# Processor.net
KiCad netlist of a schematic drawn in Altium Designer
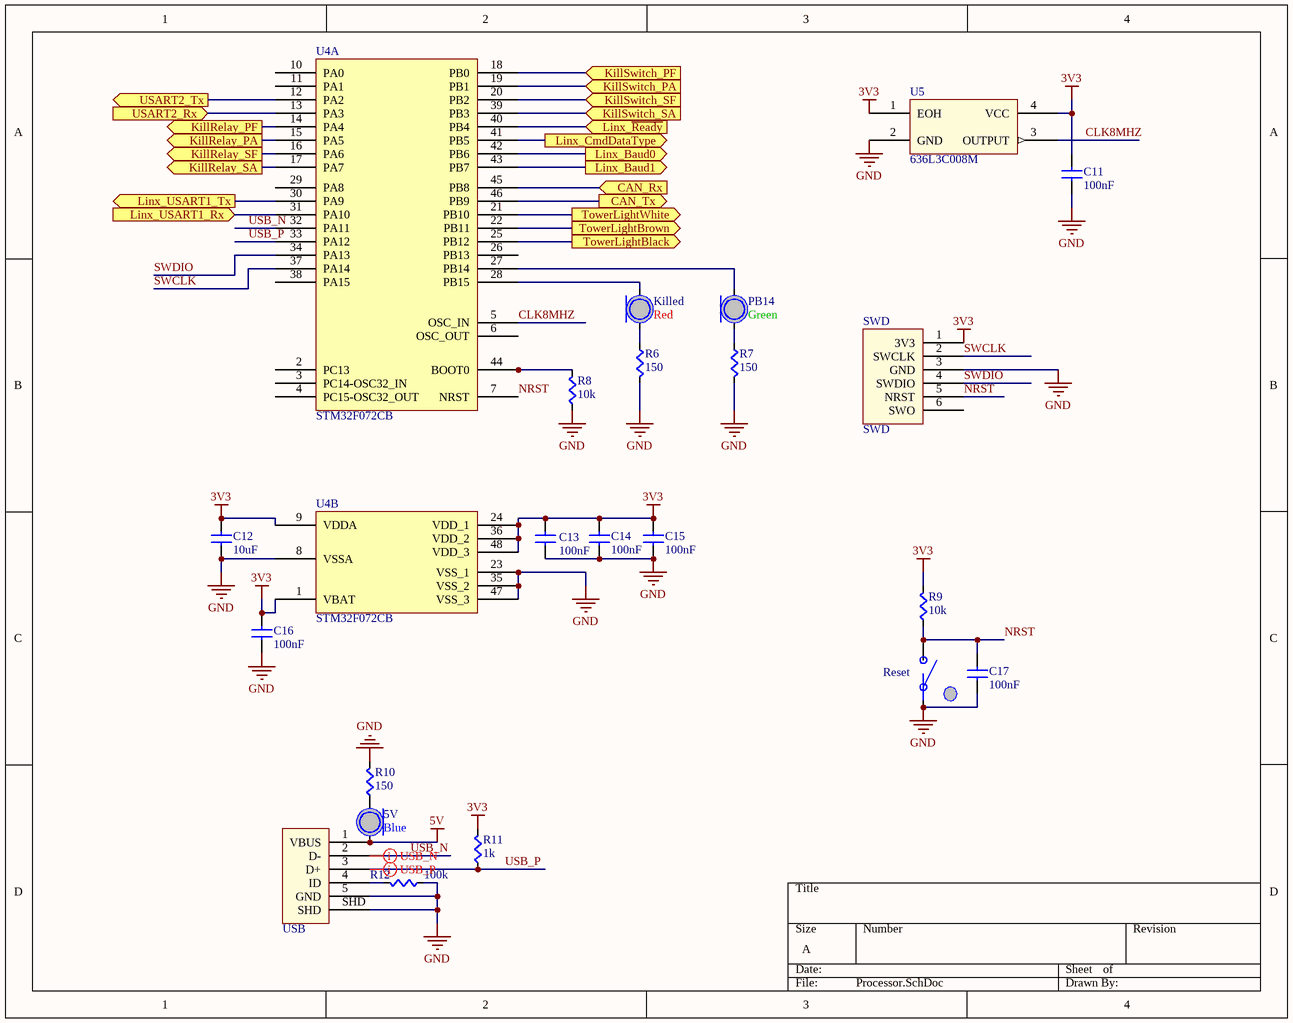
[diagram p0: Processor.SchDoc]

(export (version "E")
  (design (tool "Eeschema 10.0.6"))
  (components
    (comp (ref "5V")
      (value "LED")
      (footprint "LED0603")
      (fields (field (name "COLOR") "Blue"))
      (libsource (lib "") (part "LED_1"))
    )
    (comp (ref "C11")
      (value "100nF")
      (footprint "CAPC0603")
      (fields (field (name "Comment") "Cap"))
      (libsource (lib "SubjuGator8") (part "Cap"))
    )
    (comp (ref "C12")
      (value "10uF")
      (footprint "CAPC0603")
      (fields (field (name "Comment") "Cap"))
      (libsource (lib "SubjuGator8") (part "Cap"))
    )
    (comp (ref "C13")
      (value "100nF")
      (footprint "CAPC0603")
      (fields (field (name "Comment") "Cap"))
      (libsource (lib "SubjuGator8") (part "Cap"))
    )
    (comp (ref "C14")
      (value "100nF")
      (footprint "CAPC0603")
      (fields (field (name "Comment") "Cap"))
      (libsource (lib "SubjuGator8") (part "Cap"))
    )
    (comp (ref "C15")
      (value "100nF")
      (footprint "CAPC0603")
      (fields (field (name "Comment") "Cap"))
      (libsource (lib "SubjuGator8") (part "Cap"))
    )
    (comp (ref "C16")
      (value "100nF")
      (footprint "CAPC0603")
      (fields (field (name "Comment") "Cap"))
      (libsource (lib "SubjuGator8") (part "Cap"))
    )
    (comp (ref "C17")
      (value "100nF")
      (footprint "CAPC0603")
      (fields (field (name "Comment") "Cap"))
      (libsource (lib "SubjuGator8") (part "Cap"))
    )
    (comp (ref "Killed")
      (value "LED")
      (footprint "LED0603")
      (fields (field (name "COLOR") "Red"))
      (libsource (lib "SubjuGator8") (part "LED"))
    )
    (comp (ref "PB14")
      (value "LED")
      (footprint "LED0603")
      (fields (field (name "COLOR") "Green"))
      (libsource (lib "SubjuGator8") (part "LED"))
    )
    (comp (ref "R6")
      (value "150")
      (footprint "RES0603")
      (fields (field (name "Comment") "Res"))
      (libsource (lib "SubjuGator8") (part "Res"))
    )
    (comp (ref "R7")
      (value "150")
      (footprint "RES0603")
      (fields (field (name "Comment") "Res"))
      (libsource (lib "SubjuGator8") (part "Res"))
    )
    (comp (ref "R8")
      (value "10k")
      (footprint "RES0603")
      (fields (field (name "Comment") "Res"))
      (libsource (lib "SubjuGator8") (part "Res"))
    )
    (comp (ref "R9")
      (value "10k")
      (footprint "RES0603")
      (fields (field (name "Comment") "Res"))
      (libsource (lib "SubjuGator8") (part "Res"))
    )
    (comp (ref "R10")
      (value "150")
      (footprint "RES0603")
      (fields (field (name "Comment") "Res"))
      (libsource (lib "SubjuGator8") (part "Res"))
    )
    (comp (ref "R11")
      (value "1k")
      (footprint "RES0603")
      (fields (field (name "Comment") "Res"))
      (libsource (lib "SubjuGator8") (part "Res"))
    )
    (comp (ref "R12")
      (value "100k")
      (footprint "RES0603")
      (fields (field (name "Comment") "Res"))
      (libsource (lib "SubjuGator8") (part "Res"))
    )
    (comp (ref "Reset")
      (value "Button")
      (footprint "PTS645xxxxSMTR92")
      (description "SPST Button")
      (libsource (lib "SubjuGator8") (part "Button"))
    )
    (comp (ref "SWD")
      (value "SWD")
      (footprint "SWD_STM32")
      (description "SWD connector matching the pinout on STM Discovery Boards")
      (libsource (lib "SubjuGator8") (part "SWD_STM32"))
    )
    (comp (ref "U4")
      (value "STM32F072CB")
      (footprint "STM32F072CB")
      (description "MCU 32BIT 128KB FLASH 48LQFP")
      (libsource (lib "ICs") (part "STM32F072CB"))
    )
    (comp (ref "U5")
      (value "636L3C008M")
      (footprint "636L3C")
      (description "HCMOS/TTL Clock Oscillator")
      (libsource (lib "SubjuGator8") (part "636L3C"))
    )
    (comp (ref "USB")
      (value "USB Micro")
      (footprint "10118192-0001LF")
      (description "USB Mini B Metal Shield SMT")
      (libsource (lib "SubjuGator8") (part "USB Micro"))
    )
  )
  (nets
    (net (code "1") (name "/CAN_Rx") (class "Default")
      (node (ref "U4") (pin "45") (pinfunction "PB8_45") (pintype "passive"))
    )
    (net (code "2") (name "/CAN_Tx") (class "Default")
      (node (ref "U4") (pin "46") (pinfunction "PB9_46") (pintype "passive"))
    )
    (net (code "3") (name "/CLK8MHZ") (class "Default")
      (node (ref "U4") (pin "5") (pinfunction "OSC_IN_5") (pintype "passive"))
      (node (ref "U5") (pin "3") (pinfunction "OUTPUT_3") (pintype "output"))
    )
    (net (code "4") (name "/KillRelay_PA") (class "Default")
      (node (ref "U4") (pin "15") (pinfunction "PA5_15") (pintype "passive"))
    )
    (net (code "5") (name "/KillRelay_PF") (class "Default")
      (node (ref "U4") (pin "14") (pinfunction "PA4_14") (pintype "passive"))
    )
    (net (code "6") (name "/KillRelay_SA") (class "Default")
      (node (ref "U4") (pin "17") (pinfunction "PA7_17") (pintype "passive"))
    )
    (net (code "7") (name "/KillRelay_SF") (class "Default")
      (node (ref "U4") (pin "16") (pinfunction "PA6_16") (pintype "passive"))
    )
    (net (code "8") (name "/KillSwitch_PA") (class "Default")
      (node (ref "U4") (pin "19") (pinfunction "PB1_19") (pintype "passive"))
    )
    (net (code "9") (name "/KillSwitch_PF") (class "Default")
      (node (ref "U4") (pin "18") (pinfunction "PB0_18") (pintype "passive"))
    )
    (net (code "10") (name "/KillSwitch_SA") (class "Default")
      (node (ref "U4") (pin "39") (pinfunction "PB3_39") (pintype "passive"))
    )
    (net (code "11") (name "/KillSwitch_SF") (class "Default")
      (node (ref "U4") (pin "20") (pinfunction "PB2_20") (pintype "passive"))
    )
    (net (code "12") (name "/Linx_Baud0") (class "Default")
      (node (ref "U4") (pin "42") (pinfunction "PB6_42") (pintype "passive"))
    )
    (net (code "13") (name "/Linx_Baud1") (class "Default")
      (node (ref "U4") (pin "43") (pinfunction "PB7_43") (pintype "passive"))
    )
    (net (code "14") (name "/Linx_CmdDataType") (class "Default")
      (node (ref "U4") (pin "41") (pinfunction "PB5_41") (pintype "passive"))
    )
    (net (code "15") (name "/Linx_USART1_Rx") (class "Default")
      (node (ref "U4") (pin "31") (pinfunction "PA10_31") (pintype "passive"))
    )
    (net (code "16") (name "/Linx_USART1_Tx") (class "Default")
      (node (ref "U4") (pin "30") (pinfunction "PA9_30") (pintype "passive"))
    )
    (net (code "17") (name "/Linx_~{Ready}") (class "Default")
      (node (ref "U4") (pin "40") (pinfunction "PB4_40") (pintype "passive"))
    )
    (net (code "18") (name "/NRST") (class "Default")
      (node (ref "C17") (pin "1") (pinfunction "A_1") (pintype "passive"))
      (node (ref "R9") (pin "2") (pinfunction "B_2") (pintype "passive"))
      (node (ref "Reset") (pin "B") (pinfunction "B_B") (pintype "passive"))
      (node (ref "SWD") (pin "5") (pinfunction "NRST_5") (pintype "passive"))
      (node (ref "U4") (pin "7") (pinfunction "NRST_7") (pintype "passive"))
    )
    (net (code "19") (name "/SWCLK") (class "Default")
      (node (ref "SWD") (pin "2") (pinfunction "SWCLK_2") (pintype "passive"))
      (node (ref "U4") (pin "37") (pinfunction "PA14_37") (pintype "passive"))
    )
    (net (code "20") (name "/SWDIO") (class "Default")
      (node (ref "SWD") (pin "4") (pinfunction "SWDIO_4") (pintype "passive"))
      (node (ref "U4") (pin "34") (pinfunction "PA13_34") (pintype "passive"))
    )
    (net (code "21") (name "/TowerLightBlack") (class "Default")
      (node (ref "U4") (pin "25") (pinfunction "PB12_25") (pintype "passive"))
    )
    (net (code "22") (name "/TowerLightBrown") (class "Default")
      (node (ref "U4") (pin "22") (pinfunction "PB11_22") (pintype "passive"))
    )
    (net (code "23") (name "/TowerLightWhite") (class "Default")
      (node (ref "U4") (pin "21") (pinfunction "PB10_21") (pintype "passive"))
    )
    (net (code "24") (name "/USART2_Rx") (class "Default")
      (node (ref "U4") (pin "13") (pinfunction "PA3_13") (pintype "passive"))
    )
    (net (code "25") (name "/USART2_Tx") (class "Default")
      (node (ref "U4") (pin "12") (pinfunction "PA2_12") (pintype "passive"))
    )
    (net (code "26") (name "/USB_N") (class "Default")
      (node (ref "U4") (pin "32") (pinfunction "PA11_32") (pintype "passive"))
      (node (ref "USB") (pin "2") (pinfunction "D-_2") (pintype "passive"))
    )
    (net (code "27") (name "/USB_P") (class "Default")
      (node (ref "R11") (pin "2") (pinfunction "B_2") (pintype "passive"))
      (node (ref "U4") (pin "33") (pinfunction "PA12_33") (pintype "passive"))
      (node (ref "USB") (pin "3") (pinfunction "D+_3") (pintype "passive"))
    )
    (net (code "28") (name "3V3") (class "Default")
      (node (ref "C11") (pin "1") (pinfunction "A_1") (pintype "passive"))
      (node (ref "C12") (pin "2") (pinfunction "B_2") (pintype "passive"))
      (node (ref "C13") (pin "1") (pinfunction "A_1") (pintype "passive"))
      (node (ref "C14") (pin "1") (pinfunction "A_1") (pintype "passive"))
      (node (ref "C15") (pin "1") (pinfunction "A_1") (pintype "passive"))
      (node (ref "C16") (pin "1") (pinfunction "A_1") (pintype "passive"))
      (node (ref "R11") (pin "1") (pinfunction "A_1") (pintype "passive"))
      (node (ref "R9") (pin "1") (pinfunction "A_1") (pintype "passive"))
      (node (ref "SWD") (pin "1") (pinfunction "3V3_1") (pintype "passive"))
      (node (ref "U4") (pin "1") (pinfunction "VBAT_1") (pintype "passive"))
      (node (ref "U4") (pin "24") (pinfunction "VDD_1_24") (pintype "passive"))
      (node (ref "U4") (pin "36") (pinfunction "VDD_2_36") (pintype "passive"))
      (node (ref "U4") (pin "48") (pinfunction "VDD_3_48") (pintype "passive"))
      (node (ref "U4") (pin "9") (pinfunction "VDDA_9") (pintype "passive"))
      (node (ref "U5") (pin "1") (pinfunction "EOH_1") (pintype "passive"))
      (node (ref "U5") (pin "4") (pinfunction "VCC_4") (pintype "power_in"))
    )
    (net (code "29") (name "5V") (class "Default")
      (node (ref "5V") (pin "A") (pinfunction "A_A") (pintype "passive"))
      (node (ref "USB") (pin "1") (pinfunction "VBUS_1") (pintype "passive"))
    )
    (net (code "30") (name "GND") (class "Default")
      (node (ref "C11") (pin "2") (pinfunction "B_2") (pintype "passive"))
      (node (ref "C12") (pin "1") (pinfunction "A_1") (pintype "passive"))
      (node (ref "C13") (pin "2") (pinfunction "B_2") (pintype "passive"))
      (node (ref "C14") (pin "2") (pinfunction "B_2") (pintype "passive"))
      (node (ref "C15") (pin "2") (pinfunction "B_2") (pintype "passive"))
      (node (ref "C16") (pin "2") (pinfunction "B_2") (pintype "passive"))
      (node (ref "C17") (pin "2") (pinfunction "B_2") (pintype "passive"))
      (node (ref "R10") (pin "1") (pinfunction "A_1") (pintype "passive"))
      (node (ref "R12") (pin "2") (pinfunction "B_2") (pintype "passive"))
      (node (ref "R6") (pin "1") (pinfunction "A_1") (pintype "passive"))
      (node (ref "R7") (pin "1") (pinfunction "A_1") (pintype "passive"))
      (node (ref "R8") (pin "2") (pinfunction "B_2") (pintype "passive"))
      (node (ref "Reset") (pin "A") (pinfunction "A_A") (pintype "passive"))
      (node (ref "SWD") (pin "3") (pinfunction "GND_3") (pintype "passive"))
      (node (ref "U4") (pin "23") (pinfunction "VSS_1_23") (pintype "passive"))
      (node (ref "U4") (pin "35") (pinfunction "VSS_2_35") (pintype "passive"))
      (node (ref "U4") (pin "47") (pinfunction "VSS_3_47") (pintype "passive"))
      (node (ref "U4") (pin "8") (pinfunction "VSSA_8") (pintype "passive"))
      (node (ref "U5") (pin "2") (pinfunction "GND_2") (pintype "power_in"))
      (node (ref "USB") (pin "5") (pinfunction "GND_5") (pintype "passive"))
      (node (ref "USB") (pin "SHD") (pinfunction "SHD_SHD") (pintype "passive"))
    )
    (net (code "31") (name "Net-(R6-B)") (class "Default")
      (node (ref "Killed") (pin "C") (pinfunction "C_C") (pintype "passive"))
      (node (ref "R6") (pin "2") (pinfunction "B_2") (pintype "passive"))
    )
    (net (code "32") (name "Net-(R7-B)") (class "Default")
      (node (ref "PB14") (pin "C") (pinfunction "C_C") (pintype "passive"))
      (node (ref "R7") (pin "2") (pinfunction "B_2") (pintype "passive"))
    )
    (net (code "33") (name "Net-(R8-A)") (class "Default")
      (node (ref "R8") (pin "1") (pinfunction "A_1") (pintype "passive"))
      (node (ref "U4") (pin "44") (pinfunction "BOOT0_44") (pintype "passive"))
    )
    (net (code "34") (name "Net-(R10-B)") (class "Default")
      (node (ref "5V") (pin "C") (pinfunction "C_C") (pintype "passive"))
      (node (ref "R10") (pin "2") (pinfunction "B_2") (pintype "passive"))
    )
    (net (code "35") (name "Net-(R12-A)") (class "Default")
      (node (ref "R12") (pin "1") (pinfunction "A_1") (pintype "passive"))
      (node (ref "USB") (pin "4") (pinfunction "ID_4") (pintype "passive"))
    )
    (net (code "36") (name "Net-(U4A-PB14)") (class "Default")
      (node (ref "PB14") (pin "A") (pinfunction "A_A") (pintype "passive"))
      (node (ref "U4") (pin "27") (pinfunction "PB14_27") (pintype "passive"))
    )
    (net (code "37") (name "Net-(U4A-PB15)") (class "Default")
      (node (ref "Killed") (pin "A") (pinfunction "A_A") (pintype "passive"))
      (node (ref "U4") (pin "28") (pinfunction "PB15_28") (pintype "passive"))
    )
    (net (code "38") (name "unconnected-(SWD-SWO-Pad6)") (class "Default")
      (node (ref "SWD") (pin "6") (pinfunction "SWO_6") (pintype "passive"))
    )
    (net (code "39") (name "unconnected-(U4A-OSC_OUT-Pad6)") (class "Default")
      (node (ref "U4") (pin "6") (pinfunction "OSC_OUT_6") (pintype "passive"))
    )
    (net (code "40") (name "unconnected-(U4A-PA0-Pad10)") (class "Default")
      (node (ref "U4") (pin "10") (pinfunction "PA0_10") (pintype "passive"))
    )
    (net (code "41") (name "unconnected-(U4A-PA1-Pad11)") (class "Default")
      (node (ref "U4") (pin "11") (pinfunction "PA1_11") (pintype "passive"))
    )
    (net (code "42") (name "unconnected-(U4A-PA8-Pad29)") (class "Default")
      (node (ref "U4") (pin "29") (pinfunction "PA8_29") (pintype "passive"))
    )
    (net (code "43") (name "unconnected-(U4A-PA15-Pad38)") (class "Default")
      (node (ref "U4") (pin "38") (pinfunction "PA15_38") (pintype "passive"))
    )
    (net (code "44") (name "unconnected-(U4A-PB13-Pad26)") (class "Default")
      (node (ref "U4") (pin "26") (pinfunction "PB13_26") (pintype "passive"))
    )
    (net (code "45") (name "unconnected-(U4A-PC13-Pad2)") (class "Default")
      (node (ref "U4") (pin "2") (pinfunction "PC13_2") (pintype "passive"))
    )
    (net (code "46") (name "unconnected-(U4A-PC14-OSC32_IN-Pad3)") (class "Default")
      (node (ref "U4") (pin "3") (pinfunction "PC14-OSC32_IN_3") (pintype "passive"))
    )
    (net (code "47") (name "unconnected-(U4A-PC15-OSC32_OUT-Pad4)") (class "Default")
      (node (ref "U4") (pin "4") (pinfunction "PC15-OSC32_OUT_4") (pintype "passive"))
    )
  )
)
